# CurrentMonitor.net
KiCad netlist of a schematic drawn in EAGLE
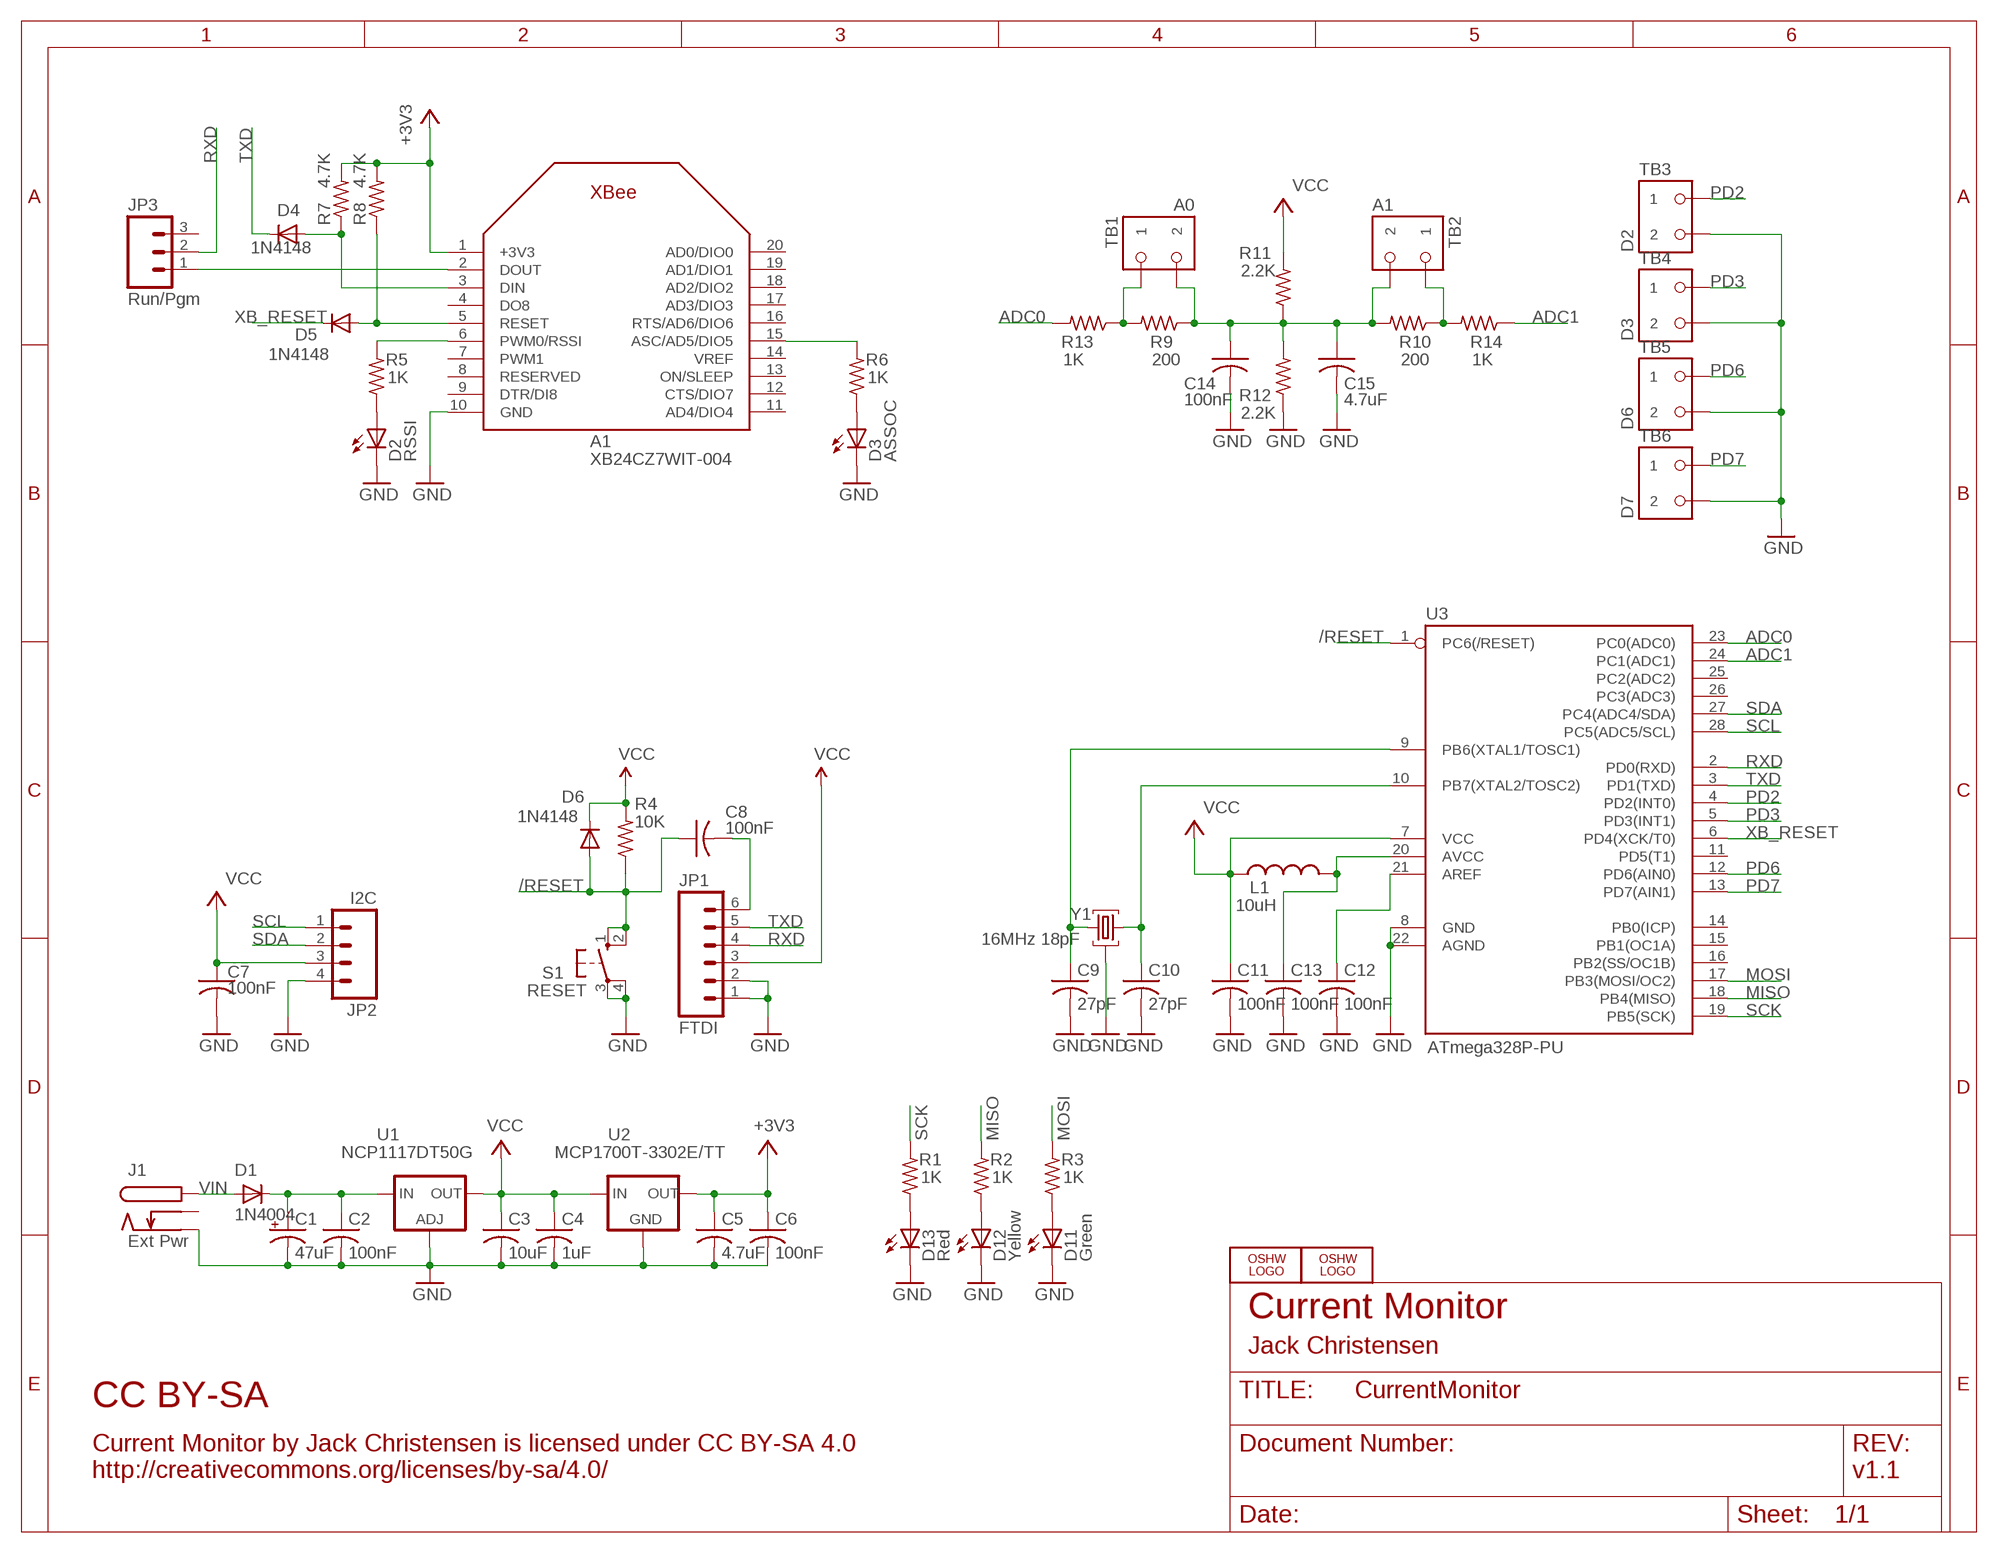
[diagram p0: schematic, sheet 1]

(export (version "E")
  (design (tool "Eeschema 10.0.6"))
  (components
    (comp (ref "A1")
      (value "XB24CZ7WIT-004")
      (footprint "eagle-import:XBEE_OVAL_PADS")
      (libsource (lib "eagle-import") (part "ULINK_XBEEOVALPADS"))
    )
    (comp (ref "C1")
      (value "47uF")
      (footprint "eagle-import:E5-5")
      (libsource (lib "eagle-import") (part "CPOL-USE5-5"))
    )
    (comp (ref "C2")
      (value "100nF")
      (footprint "eagle-import:M0805")
      (libsource (lib "eagle-import") (part "C-USM0805"))
    )
    (comp (ref "C3")
      (value "10uF")
      (footprint "eagle-import:M0805")
      (libsource (lib "eagle-import") (part "C-USM0805"))
    )
    (comp (ref "C4")
      (value "1uF")
      (footprint "eagle-import:M0805")
      (libsource (lib "eagle-import") (part "C-USM0805"))
    )
    (comp (ref "C5")
      (value "4.7uF")
      (footprint "eagle-import:M0805")
      (libsource (lib "eagle-import") (part "C-USM0805"))
    )
    (comp (ref "C6")
      (value "100nF")
      (footprint "eagle-import:M0805")
      (libsource (lib "eagle-import") (part "C-USM0805"))
    )
    (comp (ref "C7")
      (value "100nF")
      (footprint "eagle-import:M0805")
      (libsource (lib "eagle-import") (part "C-USM0805"))
    )
    (comp (ref "C8")
      (value "100nF")
      (footprint "eagle-import:M0805")
      (libsource (lib "eagle-import") (part "C-USM0805"))
    )
    (comp (ref "C9")
      (value "27pF")
      (footprint "eagle-import:M0805")
      (libsource (lib "eagle-import") (part "C-USM0805"))
    )
    (comp (ref "C10")
      (value "27pF")
      (footprint "eagle-import:M0805")
      (libsource (lib "eagle-import") (part "C-USM0805"))
    )
    (comp (ref "C11")
      (value "100nF")
      (footprint "eagle-import:M0805")
      (libsource (lib "eagle-import") (part "C-USM0805"))
    )
    (comp (ref "C12")
      (value "100nF")
      (footprint "eagle-import:M0805")
      (libsource (lib "eagle-import") (part "C-USM0805"))
    )
    (comp (ref "C13")
      (value "100nF")
      (footprint "eagle-import:M0805")
      (libsource (lib "eagle-import") (part "C-USM0805"))
    )
    (comp (ref "C14")
      (value "100nF")
      (footprint "eagle-import:M0805")
      (libsource (lib "eagle-import") (part "C-USM0805"))
    )
    (comp (ref "C15")
      (value "4.7uF")
      (footprint "eagle-import:M0805")
      (libsource (lib "eagle-import") (part "C-USM0805"))
    )
    (comp (ref "D1")
      (value "1N4004")
      (footprint "eagle-import:1N400X")
      (libsource (lib "eagle-import") (part "DIODE1N400X"))
    )
    (comp (ref "D2")
      (value "RSSI")
      (footprint "eagle-import:D0805A")
      (libsource (lib "eagle-import") (part "LEDD0805A"))
    )
    (comp (ref "D3")
      (value "ASSOC")
      (footprint "eagle-import:D0805")
      (libsource (lib "eagle-import") (part "LEDD0805"))
    )
    (comp (ref "D4")
      (value "1N4148")
      (footprint "eagle-import:SOD-323F-A")
      (libsource (lib "eagle-import") (part "DIODESOD-323F-A"))
    )
    (comp (ref "D5")
      (value "1N4148")
      (footprint "eagle-import:SOD-323F-A")
      (libsource (lib "eagle-import") (part "DIODESOD-323F-A"))
    )
    (comp (ref "D6")
      (value "1N4148")
      (footprint "eagle-import:SOD-323F")
      (libsource (lib "eagle-import") (part "DIODESOD-323F"))
    )
    (comp (ref "D11")
      (value "Green")
      (footprint "eagle-import:D0805")
      (libsource (lib "eagle-import") (part "LEDD0805"))
    )
    (comp (ref "D12")
      (value "Yellow")
      (footprint "eagle-import:D0805")
      (libsource (lib "eagle-import") (part "LEDD0805"))
    )
    (comp (ref "D13")
      (value "Red")
      (footprint "eagle-import:D0805")
      (libsource (lib "eagle-import") (part "LEDD0805"))
    )
    (comp (ref "J1")
      (value "Ext Pwr")
      (footprint "eagle-import:KLDX-0202")
      (libsource (lib "eagle-import") (part "POWER-JACK"))
    )
    (comp (ref "JP1")
      (value "FTDI")
      (footprint "eagle-import:1X06_LOCK")
      (libsource (lib "eagle-import") (part "M06LOCK"))
    )
    (comp (ref "JP2")
      (value "I2C")
      (footprint "eagle-import:1X04_LOCK")
      (libsource (lib "eagle-import") (part "M04LOCK"))
    )
    (comp (ref "JP3")
      (value "Run/Pgm")
      (footprint "eagle-import:1X03_LOCK")
      (libsource (lib "eagle-import") (part "M03LOCK"))
    )
    (comp (ref "L1")
      (value "10uH")
      (footprint "eagle-import:M0805")
      (libsource (lib "eagle-import") (part "INDUCTORM0805"))
    )
    (comp (ref "LOGO1")
      (value "OSHW_LOGO_8MILX0100-NT")
      (footprint "eagle-import:OSHW_8X100_NOTEXT")
      (libsource (lib "eagle-import") (part "OSHW_LOGO_8MILX0100-NT"))
    )
    (comp (ref "LOGO2")
      (value "OSHW_LOGO_8MILX0100-NT")
      (footprint "eagle-import:OSHW_8X100_NOTEXT")
      (libsource (lib "eagle-import") (part "OSHW_LOGO_8MILX0100-NT"))
    )
    (comp (ref "R1")
      (value "1K")
      (footprint "eagle-import:M0805")
      (libsource (lib "eagle-import") (part "R-US_M0805"))
    )
    (comp (ref "R2")
      (value "1K")
      (footprint "eagle-import:M0805")
      (libsource (lib "eagle-import") (part "R-US_M0805"))
    )
    (comp (ref "R3")
      (value "1K")
      (footprint "eagle-import:M0805")
      (libsource (lib "eagle-import") (part "R-US_M0805"))
    )
    (comp (ref "R4")
      (value "10K")
      (footprint "eagle-import:M0805")
      (libsource (lib "eagle-import") (part "R-US_M0805"))
    )
    (comp (ref "R5")
      (value "1K")
      (footprint "eagle-import:M0805")
      (libsource (lib "eagle-import") (part "R-US_M0805"))
    )
    (comp (ref "R6")
      (value "1K")
      (footprint "eagle-import:M0805")
      (libsource (lib "eagle-import") (part "R-US_M0805"))
    )
    (comp (ref "R7")
      (value "4.7K")
      (footprint "eagle-import:M0805")
      (libsource (lib "eagle-import") (part "R-US_M0805"))
    )
    (comp (ref "R8")
      (value "4.7K")
      (footprint "eagle-import:M0805")
      (libsource (lib "eagle-import") (part "R-US_M0805"))
    )
    (comp (ref "R9")
      (value "200")
      (footprint "eagle-import:M0805")
      (libsource (lib "eagle-import") (part "R-US_M0805"))
    )
    (comp (ref "R10")
      (value "200")
      (footprint "eagle-import:M0805")
      (libsource (lib "eagle-import") (part "R-US_M0805"))
    )
    (comp (ref "R11")
      (value "2.2K")
      (footprint "eagle-import:M0805")
      (libsource (lib "eagle-import") (part "R-US_M0805"))
    )
    (comp (ref "R12")
      (value "2.2K")
      (footprint "eagle-import:M0805")
      (libsource (lib "eagle-import") (part "R-US_M0805"))
    )
    (comp (ref "R13")
      (value "1K")
      (footprint "eagle-import:M0805")
      (libsource (lib "eagle-import") (part "R-US_M0805"))
    )
    (comp (ref "R14")
      (value "1K")
      (footprint "eagle-import:M0805")
      (libsource (lib "eagle-import") (part "R-US_M0805"))
    )
    (comp (ref "S1")
      (value "RESET")
      (footprint "eagle-import:B3F-10XXOCT")
      (libsource (lib "eagle-import") (part "10-XXOCT"))
    )
    (comp (ref "TB1")
      (value "A0")
      (footprint "eagle-import:OST-TB-2-3.5MM")
      (libsource (lib "eagle-import") (part "OST-TB-23.5MM"))
    )
    (comp (ref "TB2")
      (value "A1")
      (footprint "eagle-import:OST-TB-2-3.5MM")
      (libsource (lib "eagle-import") (part "OST-TB-23.5MM"))
    )
    (comp (ref "TB3")
      (value "D2")
      (footprint "eagle-import:OST-TB-2-3.5MM")
      (libsource (lib "eagle-import") (part "OST-TB-23.5MM"))
    )
    (comp (ref "TB4")
      (value "D3")
      (footprint "eagle-import:OST-TB-2-3.5MM")
      (libsource (lib "eagle-import") (part "OST-TB-23.5MM"))
    )
    (comp (ref "TB5")
      (value "D6")
      (footprint "eagle-import:OST-TB-2-3.5MM")
      (libsource (lib "eagle-import") (part "OST-TB-23.5MM"))
    )
    (comp (ref "TB6")
      (value "D7")
      (footprint "eagle-import:OST-TB-2-3.5MM")
      (libsource (lib "eagle-import") (part "OST-TB-23.5MM"))
    )
    (comp (ref "U1")
      (value "NCP1117DT50G")
      (footprint "eagle-import:DPACK")
      (libsource (lib "eagle-import") (part "LD117A?DT50TR"))
    )
    (comp (ref "U2")
      (value "MCP1700T-3302E/TT")
      (footprint "eagle-import:SOT23-W")
      (libsource (lib "eagle-import") (part "MCP1700SOT23-W"))
    )
    (comp (ref "U3")
      (value "ATmega328P-PU")
      (footprint "eagle-import:DIL28-3")
      (libsource (lib "eagle-import") (part "AVR-MEGA8-PPTH"))
    )
    (comp (ref "Y1")
      (value "16MHz 18pF")
      (footprint "eagle-import:RESONATOR")
      (libsource (lib "eagle-import") (part "RESONATOR"))
    )
  )
  (nets
    (net (code "1") (name "+3V3") (class "Default")
      (node (ref "A1") (pin "1") (pinfunction "+3V3_1") (pintype "bidirectional"))
      (node (ref "C5") (pin "1") (pinfunction "1_1") (pintype "passive"))
      (node (ref "C6") (pin "1") (pinfunction "1_1") (pintype "passive"))
      (node (ref "R7") (pin "2") (pinfunction "2_2") (pintype "passive"))
      (node (ref "R8") (pin "2") (pinfunction "2_2") (pintype "passive"))
      (node (ref "U2") (pin "2") (pinfunction "OUT_2") (pintype "passive"))
    )
    (net (code "2") (name "/ADC0") (class "Default")
      (node (ref "R13") (pin "2") (pinfunction "2_2") (pintype "passive"))
      (node (ref "U3") (pin "23") (pinfunction "PC0(ADC0)_23") (pintype "bidirectional"))
    )
    (net (code "3") (name "/ADC1") (class "Default")
      (node (ref "R14") (pin "1") (pinfunction "1_1") (pintype "passive"))
      (node (ref "U3") (pin "24") (pinfunction "PC1(ADC1)_24") (pintype "bidirectional"))
    )
    (net (code "4") (name "/MISO") (class "Default")
      (node (ref "R2") (pin "2") (pinfunction "2_2") (pintype "passive"))
      (node (ref "U3") (pin "18") (pinfunction "PB4(MISO)_18") (pintype "bidirectional"))
    )
    (net (code "5") (name "/MOSI") (class "Default")
      (node (ref "R3") (pin "2") (pinfunction "2_2") (pintype "passive"))
      (node (ref "U3") (pin "17") (pinfunction "PB3(MOSI/OC2)_17") (pintype "bidirectional"))
    )
    (net (code "6") (name "/PD2") (class "Default")
      (node (ref "TB3") (pin "P$1") (pinfunction "1_P$1") (pintype "passive"))
      (node (ref "U3") (pin "4") (pinfunction "PD2(INT0)_4") (pintype "bidirectional"))
    )
    (net (code "7") (name "/PD3") (class "Default")
      (node (ref "TB4") (pin "P$1") (pinfunction "1_P$1") (pintype "passive"))
      (node (ref "U3") (pin "5") (pinfunction "PD3(INT1)_5") (pintype "bidirectional"))
    )
    (net (code "8") (name "/PD6") (class "Default")
      (node (ref "TB5") (pin "P$1") (pinfunction "1_P$1") (pintype "passive"))
      (node (ref "U3") (pin "12") (pinfunction "PD6(AIN0)_12") (pintype "bidirectional"))
    )
    (net (code "9") (name "/PD7") (class "Default")
      (node (ref "TB6") (pin "P$1") (pinfunction "1_P$1") (pintype "passive"))
      (node (ref "U3") (pin "13") (pinfunction "PD7(AIN1)_13") (pintype "bidirectional"))
    )
    (net (code "10") (name "/RXD") (class "Default")
      (node (ref "JP1") (pin "4") (pinfunction "4_4") (pintype "passive"))
      (node (ref "JP3") (pin "2") (pinfunction "2_2") (pintype "passive"))
      (node (ref "U3") (pin "2") (pinfunction "PD0(RXD)_2") (pintype "bidirectional"))
    )
    (net (code "11") (name "/SCK") (class "Default")
      (node (ref "R1") (pin "2") (pinfunction "2_2") (pintype "passive"))
      (node (ref "U3") (pin "19") (pinfunction "PB5(SCK)_19") (pintype "bidirectional"))
    )
    (net (code "12") (name "/SCL") (class "Default")
      (node (ref "JP2") (pin "1") (pinfunction "1_1") (pintype "passive"))
      (node (ref "U3") (pin "28") (pinfunction "PC5(ADC5/SCL)_28") (pintype "bidirectional"))
    )
    (net (code "13") (name "/SDA") (class "Default")
      (node (ref "JP2") (pin "2") (pinfunction "2_2") (pintype "passive"))
      (node (ref "U3") (pin "27") (pinfunction "PC4(ADC4/SDA)_27") (pintype "bidirectional"))
    )
    (net (code "14") (name "/TXD") (class "Default")
      (node (ref "D4") (pin "K") (pinfunction "K_K") (pintype "passive"))
      (node (ref "JP1") (pin "5") (pinfunction "5_5") (pintype "passive"))
      (node (ref "U3") (pin "3") (pinfunction "PD1(TXD)_3") (pintype "bidirectional"))
    )
    (net (code "15") (name "/VIN") (class "Default")
      (node (ref "C1") (pin "+") (pinfunction "+_+") (pintype "passive"))
      (node (ref "C2") (pin "1") (pinfunction "1_1") (pintype "passive"))
      (node (ref "D1") (pin "K") (pinfunction "K_K") (pintype "passive"))
      (node (ref "U1") (pin "3") (pinfunction "IN_3") (pintype "input"))
    )
    (net (code "16") (name "/XB_RESET") (class "Default")
      (node (ref "D5") (pin "K") (pinfunction "K_K") (pintype "passive"))
      (node (ref "U3") (pin "6") (pinfunction "PD4(XCK/T0)_6") (pintype "bidirectional"))
    )
    (net (code "17") (name "/{slash}RESET") (class "Default")
      (node (ref "C8") (pin "1") (pinfunction "1_1") (pintype "passive"))
      (node (ref "D6") (pin "A") (pinfunction "A_A") (pintype "passive"))
      (node (ref "R4") (pin "1") (pinfunction "1_1") (pintype "passive"))
      (node (ref "S1") (pin "1") (pinfunction "S_1") (pintype "passive"))
      (node (ref "S1") (pin "2") (pinfunction "S1_2") (pintype "passive"))
      (node (ref "U3") (pin "1") (pinfunction "PC6(/RESET)_1") (pintype "bidirectional"))
    )
    (net (code "18") (name "GND") (class "Default")
      (node (ref "A1") (pin "10") (pinfunction "GND_10") (pintype "power_in"))
      (node (ref "C1") (pin "-") (pinfunction "-_-") (pintype "passive"))
      (node (ref "C10") (pin "2") (pinfunction "2_2") (pintype "passive"))
      (node (ref "C11") (pin "2") (pinfunction "2_2") (pintype "passive"))
      (node (ref "C12") (pin "2") (pinfunction "2_2") (pintype "passive"))
      (node (ref "C13") (pin "2") (pinfunction "2_2") (pintype "passive"))
      (node (ref "C14") (pin "2") (pinfunction "2_2") (pintype "passive"))
      (node (ref "C15") (pin "2") (pinfunction "2_2") (pintype "passive"))
      (node (ref "C2") (pin "2") (pinfunction "2_2") (pintype "passive"))
      (node (ref "C3") (pin "2") (pinfunction "2_2") (pintype "passive"))
      (node (ref "C4") (pin "2") (pinfunction "2_2") (pintype "passive"))
      (node (ref "C5") (pin "2") (pinfunction "2_2") (pintype "passive"))
      (node (ref "C6") (pin "2") (pinfunction "2_2") (pintype "passive"))
      (node (ref "C7") (pin "2") (pinfunction "2_2") (pintype "passive"))
      (node (ref "C9") (pin "2") (pinfunction "2_2") (pintype "passive"))
      (node (ref "D11") (pin "K") (pinfunction "C_K") (pintype "passive"))
      (node (ref "D12") (pin "K") (pinfunction "C_K") (pintype "passive"))
      (node (ref "D13") (pin "K") (pinfunction "C_K") (pintype "passive"))
      (node (ref "D2") (pin "K") (pinfunction "C_K") (pintype "passive"))
      (node (ref "D3") (pin "K") (pinfunction "C_K") (pintype "passive"))
      (node (ref "J1") (pin "P$2") (pinfunction "P$2_P$2") (pintype "bidirectional"))
      (node (ref "JP1") (pin "1") (pinfunction "1_1") (pintype "passive"))
      (node (ref "JP1") (pin "2") (pinfunction "2_2") (pintype "passive"))
      (node (ref "JP2") (pin "4") (pinfunction "4_4") (pintype "passive"))
      (node (ref "R12") (pin "1") (pinfunction "1_1") (pintype "passive"))
      (node (ref "S1") (pin "3") (pinfunction "P_3") (pintype "passive"))
      (node (ref "S1") (pin "4") (pinfunction "P1_4") (pintype "passive"))
      (node (ref "TB3") (pin "P$2") (pinfunction "2_P$2") (pintype "passive"))
      (node (ref "TB4") (pin "P$2") (pinfunction "2_P$2") (pintype "passive"))
      (node (ref "TB5") (pin "P$2") (pinfunction "2_P$2") (pintype "passive"))
      (node (ref "TB6") (pin "P$2") (pinfunction "2_P$2") (pintype "passive"))
      (node (ref "U1") (pin "1") (pinfunction "ADJ_1") (pintype "input"))
      (node (ref "U2") (pin "1") (pinfunction "GND_1") (pintype "input"))
      (node (ref "U3") (pin "22") (pinfunction "AGND_22") (pintype "bidirectional"))
      (node (ref "U3") (pin "8") (pinfunction "GND_8") (pintype "bidirectional"))
      (node (ref "Y1") (pin "2") (pinfunction "2_2") (pintype "passive"))
    )
    (net (code "19") (name "Net-(A1-ASC{slash}AD5{slash}DIO5)") (class "Default")
      (node (ref "A1") (pin "15") (pinfunction "ASC/AD5/DIO5_15") (pintype "bidirectional"))
      (node (ref "R6") (pin "2") (pinfunction "2_2") (pintype "passive"))
    )
    (net (code "20") (name "Net-(A1-DIN)") (class "Default")
      (node (ref "A1") (pin "3") (pinfunction "DIN_3") (pintype "input"))
      (node (ref "D4") (pin "A") (pinfunction "A_A") (pintype "passive"))
      (node (ref "R7") (pin "1") (pinfunction "1_1") (pintype "passive"))
    )
    (net (code "21") (name "Net-(A1-DOUT)") (class "Default")
      (node (ref "A1") (pin "2") (pinfunction "DOUT_2") (pintype "output"))
      (node (ref "JP3") (pin "1") (pinfunction "1_1") (pintype "passive"))
    )
    (net (code "22") (name "Net-(A1-PWM0{slash}RSSI)") (class "Default")
      (node (ref "A1") (pin "6") (pinfunction "PWM0/RSSI_6") (pintype "bidirectional"))
      (node (ref "R5") (pin "2") (pinfunction "2_2") (pintype "passive"))
    )
    (net (code "23") (name "Net-(A1-RESET)") (class "Default")
      (node (ref "A1") (pin "5") (pinfunction "RESET_5") (pintype "bidirectional"))
      (node (ref "D5") (pin "A") (pinfunction "A_A") (pintype "passive"))
      (node (ref "R8") (pin "1") (pinfunction "1_1") (pintype "passive"))
    )
    (net (code "24") (name "Net-(C8-Pad2)") (class "Default")
      (node (ref "C8") (pin "2") (pinfunction "2_2") (pintype "passive"))
      (node (ref "JP1") (pin "6") (pinfunction "6_6") (pintype "passive"))
    )
    (net (code "25") (name "Net-(D1-PadA)") (class "Default")
      (node (ref "D1") (pin "A") (pinfunction "A_A") (pintype "passive"))
      (node (ref "J1") (pin "P$1") (pinfunction "P$1_P$1") (pintype "bidirectional"))
    )
    (net (code "26") (name "Net-(D2-PadA)") (class "Default")
      (node (ref "D2") (pin "A") (pinfunction "A_A") (pintype "passive"))
      (node (ref "R5") (pin "1") (pinfunction "1_1") (pintype "passive"))
    )
    (net (code "27") (name "Net-(D3-PadA)") (class "Default")
      (node (ref "D3") (pin "A") (pinfunction "A_A") (pintype "passive"))
      (node (ref "R6") (pin "1") (pinfunction "1_1") (pintype "passive"))
    )
    (net (code "28") (name "Net-(D11-PadA)") (class "Default")
      (node (ref "D11") (pin "A") (pinfunction "A_A") (pintype "passive"))
      (node (ref "R3") (pin "1") (pinfunction "1_1") (pintype "passive"))
    )
    (net (code "29") (name "Net-(D12-PadA)") (class "Default")
      (node (ref "D12") (pin "A") (pinfunction "A_A") (pintype "passive"))
      (node (ref "R2") (pin "1") (pinfunction "1_1") (pintype "passive"))
    )
    (net (code "30") (name "Net-(D13-PadA)") (class "Default")
      (node (ref "D13") (pin "A") (pinfunction "A_A") (pintype "passive"))
      (node (ref "R1") (pin "1") (pinfunction "1_1") (pintype "passive"))
    )
    (net (code "31") (name "Net-(TB1-1)") (class "Default")
      (node (ref "R13") (pin "1") (pinfunction "1_1") (pintype "passive"))
      (node (ref "R9") (pin "2") (pinfunction "2_2") (pintype "passive"))
      (node (ref "TB1") (pin "P$1") (pinfunction "1_P$1") (pintype "passive"))
    )
    (net (code "32") (name "Net-(TB1-2)") (class "Default")
      (node (ref "C14") (pin "1") (pinfunction "1_1") (pintype "passive"))
      (node (ref "C15") (pin "1") (pinfunction "1_1") (pintype "passive"))
      (node (ref "R10") (pin "2") (pinfunction "2_2") (pintype "passive"))
      (node (ref "R11") (pin "1") (pinfunction "1_1") (pintype "passive"))
      (node (ref "R12") (pin "2") (pinfunction "2_2") (pintype "passive"))
      (node (ref "R9") (pin "1") (pinfunction "1_1") (pintype "passive"))
      (node (ref "TB1") (pin "P$2") (pinfunction "2_P$2") (pintype "passive"))
      (node (ref "TB2") (pin "P$2") (pinfunction "2_P$2") (pintype "passive"))
    )
    (net (code "33") (name "Net-(TB2-1)") (class "Default")
      (node (ref "R10") (pin "1") (pinfunction "1_1") (pintype "passive"))
      (node (ref "R14") (pin "2") (pinfunction "2_2") (pintype "passive"))
      (node (ref "TB2") (pin "P$1") (pinfunction "1_P$1") (pintype "passive"))
    )
    (net (code "34") (name "Net-(U3-AREF)") (class "Default")
      (node (ref "C12") (pin "1") (pinfunction "1_1") (pintype "passive"))
      (node (ref "U3") (pin "21") (pinfunction "AREF_21") (pintype "bidirectional"))
    )
    (net (code "35") (name "Net-(U3-AVCC)") (class "Default")
      (node (ref "C13") (pin "1") (pinfunction "1_1") (pintype "passive"))
      (node (ref "L1") (pin "2") (pinfunction "2_2") (pintype "passive"))
      (node (ref "U3") (pin "20") (pinfunction "AVCC_20") (pintype "bidirectional"))
    )
    (net (code "36") (name "Net-(U3-PB6(XTAL1{slash}TOSC1))") (class "Default")
      (node (ref "C9") (pin "1") (pinfunction "1_1") (pintype "passive"))
      (node (ref "U3") (pin "9") (pinfunction "PB6(XTAL1/TOSC1)_9") (pintype "bidirectional"))
      (node (ref "Y1") (pin "1") (pinfunction "1_1") (pintype "passive"))
    )
    (net (code "37") (name "Net-(U3-PB7(XTAL2{slash}TOSC2))") (class "Default")
      (node (ref "C10") (pin "1") (pinfunction "1_1") (pintype "passive"))
      (node (ref "U3") (pin "10") (pinfunction "PB7(XTAL2/TOSC2)_10") (pintype "bidirectional"))
      (node (ref "Y1") (pin "3") (pinfunction "3_3") (pintype "passive"))
    )
    (net (code "38") (name "VCC") (class "Default")
      (node (ref "C11") (pin "1") (pinfunction "1_1") (pintype "passive"))
      (node (ref "C3") (pin "1") (pinfunction "1_1") (pintype "passive"))
      (node (ref "C4") (pin "1") (pinfunction "1_1") (pintype "passive"))
      (node (ref "C7") (pin "1") (pinfunction "1_1") (pintype "passive"))
      (node (ref "D6") (pin "K") (pinfunction "K_K") (pintype "passive"))
      (node (ref "JP1") (pin "3") (pinfunction "3_3") (pintype "passive"))
      (node (ref "JP2") (pin "3") (pinfunction "3_3") (pintype "passive"))
      (node (ref "L1") (pin "1") (pinfunction "1_1") (pintype "passive"))
      (node (ref "R11") (pin "2") (pinfunction "2_2") (pintype "passive"))
      (node (ref "R4") (pin "2") (pinfunction "2_2") (pintype "passive"))
      (node (ref "U1") (pin "4") (pinfunction "OUT_4") (pintype "passive"))
      (node (ref "U2") (pin "3") (pinfunction "IN_3") (pintype "input"))
      (node (ref "U3") (pin "7") (pinfunction "VCC_7") (pintype "bidirectional"))
    )
    (net (code "39") (name "unconnected-(A1-AD0{slash}DIO0-Pad20)") (class "Default")
      (node (ref "A1") (pin "20") (pinfunction "AD0/DIO0_20") (pintype "bidirectional"))
    )
    (net (code "40") (name "unconnected-(A1-AD1{slash}DIO1-Pad19)") (class "Default")
      (node (ref "A1") (pin "19") (pinfunction "AD1/DIO1_19") (pintype "bidirectional"))
    )
    (net (code "41") (name "unconnected-(A1-AD2{slash}DIO2-Pad18)") (class "Default")
      (node (ref "A1") (pin "18") (pinfunction "AD2/DIO2_18") (pintype "bidirectional"))
    )
    (net (code "42") (name "unconnected-(A1-AD3{slash}DIO3-Pad17)") (class "Default")
      (node (ref "A1") (pin "17") (pinfunction "AD3/DIO3_17") (pintype "bidirectional"))
    )
    (net (code "43") (name "unconnected-(A1-AD4{slash}DIO4-Pad11)") (class "Default")
      (node (ref "A1") (pin "11") (pinfunction "AD4/DIO4_11") (pintype "bidirectional"))
    )
    (net (code "44") (name "unconnected-(A1-CTS{slash}DIO7-Pad12)") (class "Default")
      (node (ref "A1") (pin "12") (pinfunction "CTS/DIO7_12") (pintype "bidirectional"))
    )
    (net (code "45") (name "unconnected-(A1-DO8-Pad4)") (class "Default")
      (node (ref "A1") (pin "4") (pinfunction "DO8_4") (pintype "output"))
    )
    (net (code "46") (name "unconnected-(A1-DTR{slash}DI8-Pad9)") (class "Default")
      (node (ref "A1") (pin "9") (pinfunction "DTR/DI8_9") (pintype "bidirectional"))
    )
    (net (code "47") (name "unconnected-(A1-ON{slash}SLEEP-Pad13)") (class "Default")
      (node (ref "A1") (pin "13") (pinfunction "ON/SLEEP_13") (pintype "output"))
    )
    (net (code "48") (name "unconnected-(A1-PWM1-Pad7)") (class "Default")
      (node (ref "A1") (pin "7") (pinfunction "PWM1_7") (pintype "bidirectional"))
    )
    (net (code "49") (name "unconnected-(A1-RESERVED-Pad8)") (class "Default")
      (node (ref "A1") (pin "8") (pinfunction "RESERVED_8") (pintype "no_connect"))
    )
    (net (code "50") (name "unconnected-(A1-RTS{slash}AD6{slash}DIO6-Pad16)") (class "Default")
      (node (ref "A1") (pin "16") (pinfunction "RTS/AD6/DIO6_16") (pintype "bidirectional"))
    )
    (net (code "51") (name "unconnected-(A1-VREF-Pad14)") (class "Default")
      (node (ref "A1") (pin "14") (pinfunction "VREF_14") (pintype "bidirectional"))
    )
    (net (code "52") (name "unconnected-(J1-PadP$3)") (class "Default")
      (node (ref "J1") (pin "P$3") (pinfunction "P$3_P$3") (pintype "bidirectional"))
    )
    (net (code "53") (name "unconnected-(JP3-Pad3)") (class "Default")
      (node (ref "JP3") (pin "3") (pinfunction "3_3") (pintype "passive"))
    )
    (net (code "54") (name "unconnected-(U3-PB0(ICP)-Pad14)") (class "Default")
      (node (ref "U3") (pin "14") (pinfunction "PB0(ICP)_14") (pintype "bidirectional"))
    )
    (net (code "55") (name "unconnected-(U3-PB1(OC1A)-Pad15)") (class "Default")
      (node (ref "U3") (pin "15") (pinfunction "PB1(OC1A)_15") (pintype "bidirectional"))
    )
    (net (code "56") (name "unconnected-(U3-PB2(SS{slash}OC1B)-Pad16)") (class "Default")
      (node (ref "U3") (pin "16") (pinfunction "PB2(SS/OC1B)_16") (pintype "bidirectional"))
    )
    (net (code "57") (name "unconnected-(U3-PC2(ADC2)-Pad25)") (class "Default")
      (node (ref "U3") (pin "25") (pinfunction "PC2(ADC2)_25") (pintype "bidirectional"))
    )
    (net (code "58") (name "unconnected-(U3-PC3(ADC3)-Pad26)") (class "Default")
      (node (ref "U3") (pin "26") (pinfunction "PC3(ADC3)_26") (pintype "bidirectional"))
    )
    (net (code "59") (name "unconnected-(U3-PD5(T1)-Pad11)") (class "Default")
      (node (ref "U3") (pin "11") (pinfunction "PD5(T1)_11") (pintype "bidirectional"))
    )
  )
)
